# Schematic.net
KiCad netlist of a schematic drawn in Altium Designer
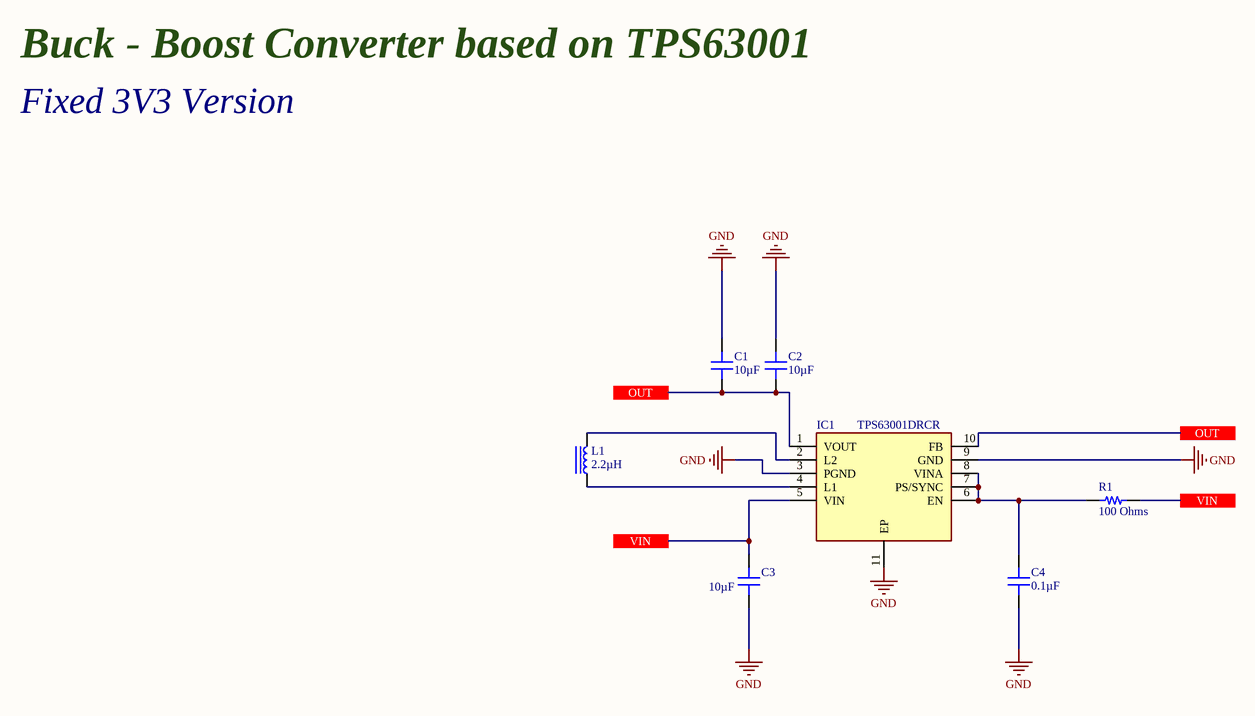
[diagram p0: Schematic.SchDoc]

(export (version "E")
  (design (tool "Eeschema 10.0.6"))
  (components
    (comp (ref "C1")
      (value "10µF")
      (footprint "CAP 0603_1608")
      (description "CAP CER 10UF 6.3V X7R 0603")
      (fields
        (field (name "PART NUMBER") "CL10B106MQ8NRNC")
        (field (name "MANUFACTURER") "Samsung Electro-Mechanics")
      )
      (libsource (lib "Celestial Altium Library - altium_library") (part "Capacitor"))
    )
    (comp (ref "C2")
      (value "10µF")
      (footprint "CAP 0603_1608")
      (description "CAP CER 10UF 6.3V X7R 0603")
      (fields
        (field (name "PART NUMBER") "CL10B106MQ8NRNC")
        (field (name "MANUFACTURER") "Samsung Electro-Mechanics")
      )
      (libsource (lib "Celestial Altium Library - altium_library") (part "Capacitor"))
    )
    (comp (ref "C3")
      (value "10µF")
      (footprint "CAP 0603_1608")
      (description "CAP CER 10UF 6.3V X7R 0603")
      (fields
        (field (name "PART NUMBER") "CL10B106MQ8NRNC")
        (field (name "MANUFACTURER") "Samsung Electro-Mechanics")
      )
      (libsource (lib "Celestial Altium Library - altium_library") (part "Capacitor"))
    )
    (comp (ref "C4")
      (value "0.1µF")
      (footprint "CAP 0603_1608")
      (description "CAP CER 0.1UF 10V X7R 0603")
      (fields (field (name "PART NUMBER") "C0603C104K8RACTU") (field (name "MANUFACTURER") "KEMET"))
      (libsource (lib "Celestial Altium Library - altium_library") (part "Capacitor"))
    )
    (comp (ref "IC1")
      (value "TPS63001DRCR")
      (footprint "SamacSys:SON50P300X300X100-11N-D")
      (description "Integrated Circuit")
      (libsource (lib "*") (part "TPS63001DRCR"))
    )
    (comp (ref "L1")
      (value "2.2µH")
      (footprint "TDK SPM3012-LR")
      (description "FIXED IND 2.2UH 2.8A 86.6 MOHM")
      (fields (field (name "PART NUMBER") "SPM3015T-2R2M-LR") (field (name "MANUFACTURER") "TDK Corporation"))
      (libsource (lib "Celestial Altium Library - altium_library") (part "Inductor"))
    )
    (comp (ref "R1")
      (value "100 Ohms")
      (footprint "RES 0603_1608")
      (description "RES 100 OHM 0.1% 1/16W 0603")
      (fields
        (field (name "PART NUMBER") "RNCS0603BKE100R")
        (field (name "MANUFACTURER") "Stackpole Electronics Inc")
      )
      (libsource (lib "Celestial Altium Library - altium_library") (part "Resistor"))
    )
  )
  (nets
    (net (code "1") (name "/OUT") (class "Default")
      (node (ref "C1") (pin "2") (pinfunction "2_2") (pintype "passive"))
      (node (ref "C2") (pin "2") (pinfunction "2_2") (pintype "passive"))
      (node (ref "IC1") (pin "1") (pinfunction "VOUT_1") (pintype "passive"))
      (node (ref "IC1") (pin "10") (pinfunction "FB_10") (pintype "passive"))
    )
    (net (code "2") (name "/VIN") (class "Default")
      (node (ref "C3") (pin "1") (pinfunction "1_1") (pintype "passive"))
      (node (ref "IC1") (pin "5") (pinfunction "VIN_5") (pintype "passive"))
      (node (ref "R1") (pin "1") (pinfunction "1_1") (pintype "passive"))
    )
    (net (code "3") (name "GND") (class "Default")
      (node (ref "C1") (pin "1") (pinfunction "1_1") (pintype "passive"))
      (node (ref "C2") (pin "1") (pinfunction "1_1") (pintype "passive"))
      (node (ref "C3") (pin "2") (pinfunction "2_2") (pintype "passive"))
      (node (ref "C4") (pin "1") (pinfunction "1_1") (pintype "passive"))
      (node (ref "IC1") (pin "11") (pinfunction "EP_11") (pintype "passive"))
      (node (ref "IC1") (pin "3") (pinfunction "PGND_3") (pintype "passive"))
      (node (ref "IC1") (pin "9") (pinfunction "GND_9") (pintype "passive"))
    )
    (net (code "4") (name "Net-(IC1-EN)") (class "Default")
      (node (ref "C4") (pin "2") (pinfunction "2_2") (pintype "passive"))
      (node (ref "IC1") (pin "6") (pinfunction "EN_6") (pintype "passive"))
      (node (ref "IC1") (pin "7") (pinfunction "PS/SYNC_7") (pintype "passive"))
      (node (ref "IC1") (pin "8") (pinfunction "VINA_8") (pintype "passive"))
      (node (ref "R1") (pin "2") (pinfunction "2_2") (pintype "passive"))
    )
    (net (code "5") (name "Net-(IC1-L1)") (class "Default")
      (node (ref "IC1") (pin "4") (pinfunction "L1_4") (pintype "passive"))
      (node (ref "L1") (pin "1") (pinfunction "1_1") (pintype "passive"))
    )
    (net (code "6") (name "Net-(IC1-L2)") (class "Default")
      (node (ref "IC1") (pin "2") (pinfunction "L2_2") (pintype "passive"))
      (node (ref "L1") (pin "2") (pinfunction "2_2") (pintype "passive"))
    )
  )
)
